# power.net
KiCad netlist of a schematic drawn in EAGLE
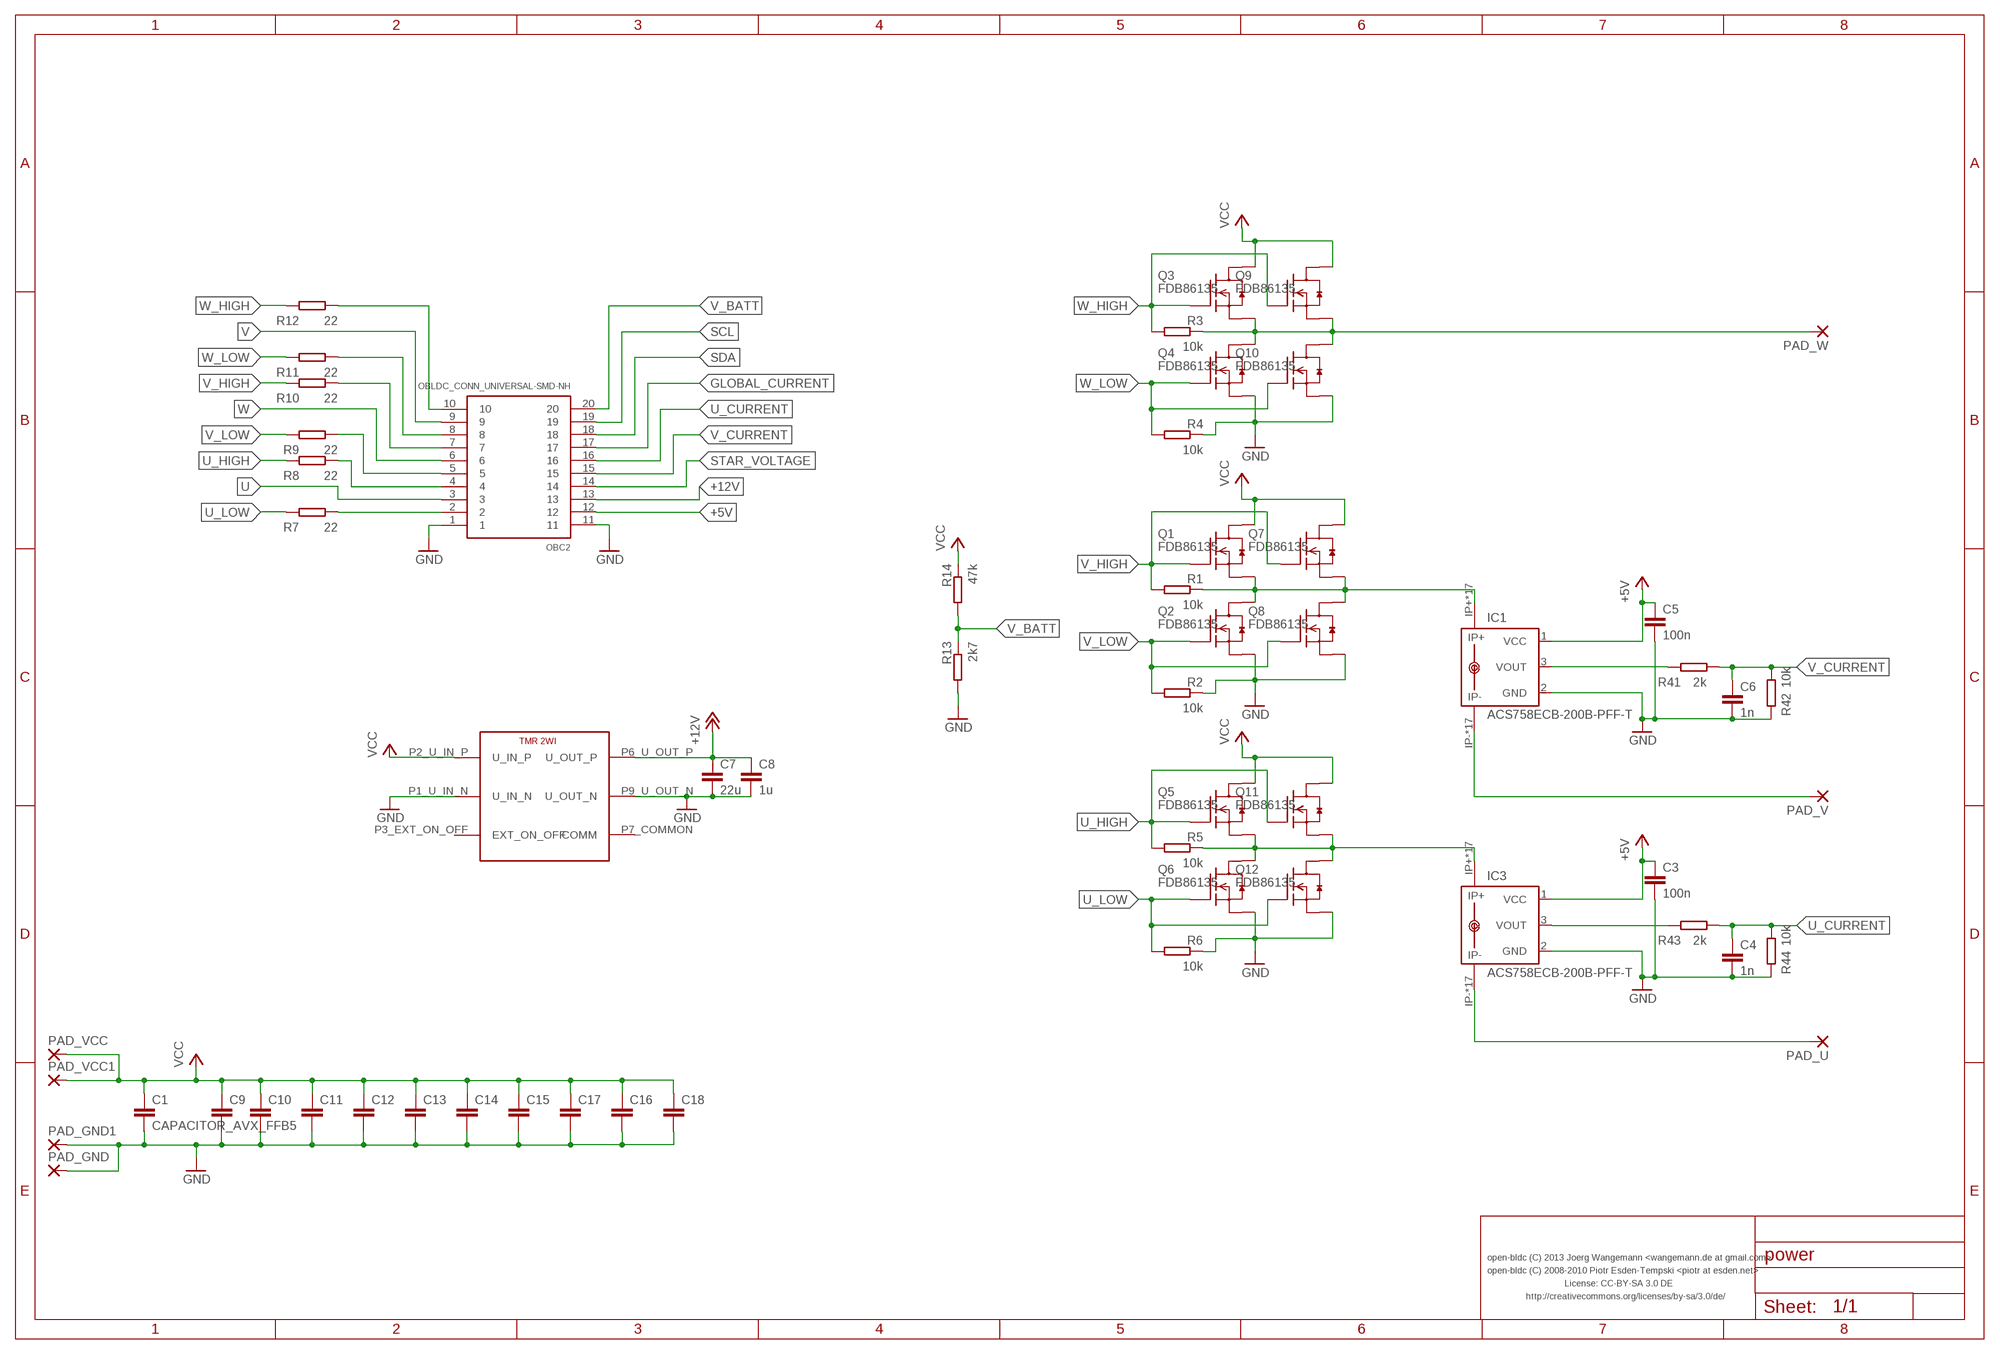
[diagram p0: schematic, sheet 1]

(export (version "E")
  (design (tool "Eeschema 10.0.6"))
  (components
    (comp (ref "C1")
      (value "CAPACITOR_AVX_FFB5")
      (footprint "eagle-import:AVX_FFB5")
      (libsource (lib "eagle-import") (part "CAPACITOR_AVX_FFB5"))
    )
    (comp (ref "C3")
      (value "100n")
      (footprint "eagle-import:0603-CAP")
      (libsource (lib "eagle-import") (part "CAPACITOR-0603"))
    )
    (comp (ref "C4")
      (value "1n")
      (footprint "eagle-import:0603-CAP")
      (libsource (lib "eagle-import") (part "CAPACITOR-0603"))
    )
    (comp (ref "C5")
      (value "100n")
      (footprint "eagle-import:0603-CAP")
      (libsource (lib "eagle-import") (part "CAPACITOR-0603"))
    )
    (comp (ref "C6")
      (value "1n")
      (footprint "eagle-import:0603-CAP")
      (libsource (lib "eagle-import") (part "CAPACITOR-0603"))
    )
    (comp (ref "C7")
      (value "22u")
      (footprint "eagle-import:C2220K")
      (libsource (lib "eagle-import") (part "C-EUC2220K"))
    )
    (comp (ref "C8")
      (value "1u")
      (footprint "eagle-import:C1206")
      (libsource (lib "eagle-import") (part "C-EUC1206"))
    )
    (comp (ref "C9")
      (value "C-EUC2220K")
      (footprint "eagle-import:C2220K")
      (libsource (lib "eagle-import") (part "C-EUC2220K"))
    )
    (comp (ref "C10")
      (value "C-EUC2220K")
      (footprint "eagle-import:C2220K")
      (libsource (lib "eagle-import") (part "C-EUC2220K"))
    )
    (comp (ref "C11")
      (value "C-EUC2220K")
      (footprint "eagle-import:C2220K")
      (libsource (lib "eagle-import") (part "C-EUC2220K"))
    )
    (comp (ref "C12")
      (value "C-EUC2220K")
      (footprint "eagle-import:C2220K")
      (libsource (lib "eagle-import") (part "C-EUC2220K"))
    )
    (comp (ref "C13")
      (value "C-EUC2220K")
      (footprint "eagle-import:C2220K")
      (libsource (lib "eagle-import") (part "C-EUC2220K"))
    )
    (comp (ref "C14")
      (value "C-EUC2220K")
      (footprint "eagle-import:C2220K")
      (libsource (lib "eagle-import") (part "C-EUC2220K"))
    )
    (comp (ref "C15")
      (value "C-EUC2220K")
      (footprint "eagle-import:C2220K")
      (libsource (lib "eagle-import") (part "C-EUC2220K"))
    )
    (comp (ref "C16")
      (value "C-EUC2220K")
      (footprint "eagle-import:C2220K")
      (libsource (lib "eagle-import") (part "C-EUC2220K"))
    )
    (comp (ref "C17")
      (value "C-EUC2220K")
      (footprint "eagle-import:C2220K")
      (libsource (lib "eagle-import") (part "C-EUC2220K"))
    )
    (comp (ref "C18")
      (value "C-EUC2220K")
      (footprint "eagle-import:C2220K")
      (libsource (lib "eagle-import") (part "C-EUC2220K"))
    )
    (comp (ref "IC1")
      (value "ACS758ECB-200B-PFF-T")
      (footprint "eagle-import:CB-PFF")
      (libsource (lib "eagle-import") (part "ACS758ECB-200B-PFF-T"))
    )
    (comp (ref "IC3")
      (value "ACS758ECB-200B-PFF-T")
      (footprint "eagle-import:CB-PFF")
      (libsource (lib "eagle-import") (part "ACS758ECB-200B-PFF-T"))
    )
    (comp (ref "OBC2")
      (value "OBLDC_CONN_UNIVERSAL-SMD-NH")
      (footprint "eagle-import:OBLDC_CONN_SMD_NO_HOLES")
      (libsource (lib "eagle-import") (part "OBLDC_CONN_UNIVERSAL-SMD-NH"))
    )
    (comp (ref "PAD_GND")
      (value "WIREPAD-2MM")
      (footprint "eagle-import:WIREPAD_2MM")
      (libsource (lib "eagle-import") (part "WIREPAD-2MM"))
    )
    (comp (ref "PAD_GND1")
      (value "WIREPAD-2MM")
      (footprint "eagle-import:WIREPAD_2MM")
      (libsource (lib "eagle-import") (part "WIREPAD-2MM"))
    )
    (comp (ref "PAD_U")
      (value "WIREPAD-2MM")
      (footprint "eagle-import:WIREPAD_2MM")
      (libsource (lib "eagle-import") (part "WIREPAD-2MM"))
    )
    (comp (ref "PAD_V")
      (value "WIREPAD-2MM")
      (footprint "eagle-import:WIREPAD_2MM")
      (libsource (lib "eagle-import") (part "WIREPAD-2MM"))
    )
    (comp (ref "PAD_VCC")
      (value "WIREPAD-2MM")
      (footprint "eagle-import:WIREPAD_2MM")
      (libsource (lib "eagle-import") (part "WIREPAD-2MM"))
    )
    (comp (ref "PAD_VCC1")
      (value "WIREPAD-2MM")
      (footprint "eagle-import:WIREPAD_2MM")
      (libsource (lib "eagle-import") (part "WIREPAD-2MM"))
    )
    (comp (ref "PAD_W")
      (value "WIREPAD-2MM")
      (footprint "eagle-import:WIREPAD_2MM")
      (libsource (lib "eagle-import") (part "WIREPAD-2MM"))
    )
    (comp (ref "Q1")
      (value "FDB86135")
      (footprint "eagle-import:DPAK")
      (libsource (lib "eagle-import") (part "FDB86135"))
    )
    (comp (ref "Q2")
      (value "FDB86135")
      (footprint "eagle-import:DPAK")
      (libsource (lib "eagle-import") (part "FDB86135"))
    )
    (comp (ref "Q3")
      (value "FDB86135")
      (footprint "eagle-import:DPAK")
      (libsource (lib "eagle-import") (part "FDB86135"))
    )
    (comp (ref "Q4")
      (value "FDB86135")
      (footprint "eagle-import:DPAK")
      (libsource (lib "eagle-import") (part "FDB86135"))
    )
    (comp (ref "Q5")
      (value "FDB86135")
      (footprint "eagle-import:DPAK")
      (libsource (lib "eagle-import") (part "FDB86135"))
    )
    (comp (ref "Q6")
      (value "FDB86135")
      (footprint "eagle-import:DPAK")
      (libsource (lib "eagle-import") (part "FDB86135"))
    )
    (comp (ref "Q7")
      (value "FDB86135")
      (footprint "eagle-import:DPAK")
      (libsource (lib "eagle-import") (part "FDB86135"))
    )
    (comp (ref "Q8")
      (value "FDB86135")
      (footprint "eagle-import:DPAK")
      (libsource (lib "eagle-import") (part "FDB86135"))
    )
    (comp (ref "Q9")
      (value "FDB86135")
      (footprint "eagle-import:DPAK")
      (libsource (lib "eagle-import") (part "FDB86135"))
    )
    (comp (ref "Q10")
      (value "FDB86135")
      (footprint "eagle-import:DPAK")
      (libsource (lib "eagle-import") (part "FDB86135"))
    )
    (comp (ref "Q11")
      (value "FDB86135")
      (footprint "eagle-import:DPAK")
      (libsource (lib "eagle-import") (part "FDB86135"))
    )
    (comp (ref "Q12")
      (value "FDB86135")
      (footprint "eagle-import:DPAK")
      (libsource (lib "eagle-import") (part "FDB86135"))
    )
    (comp (ref "R1")
      (value "10k")
      (footprint "eagle-import:0603-SF-RES")
      (libsource (lib "eagle-import") (part "RESISTOR-0603SF"))
    )
    (comp (ref "R2")
      (value "10k")
      (footprint "eagle-import:0603-SF-RES")
      (libsource (lib "eagle-import") (part "RESISTOR-0603SF"))
    )
    (comp (ref "R3")
      (value "10k")
      (footprint "eagle-import:0603-SF-RES")
      (libsource (lib "eagle-import") (part "RESISTOR-0603SF"))
    )
    (comp (ref "R4")
      (value "10k")
      (footprint "eagle-import:0603-SF-RES")
      (libsource (lib "eagle-import") (part "RESISTOR-0603SF"))
    )
    (comp (ref "R5")
      (value "10k")
      (footprint "eagle-import:0603-SF-RES")
      (libsource (lib "eagle-import") (part "RESISTOR-0603SF"))
    )
    (comp (ref "R6")
      (value "10k")
      (footprint "eagle-import:0603-SF-RES")
      (libsource (lib "eagle-import") (part "RESISTOR-0603SF"))
    )
    (comp (ref "R7")
      (value "22")
      (footprint "eagle-import:1206-RES")
      (libsource (lib "eagle-import") (part "RESISTOR-1206"))
    )
    (comp (ref "R8")
      (value "22")
      (footprint "eagle-import:1206-RES")
      (libsource (lib "eagle-import") (part "RESISTOR-1206"))
    )
    (comp (ref "R9")
      (value "22")
      (footprint "eagle-import:1206-RES")
      (libsource (lib "eagle-import") (part "RESISTOR-1206"))
    )
    (comp (ref "R10")
      (value "22")
      (footprint "eagle-import:1206-RES")
      (libsource (lib "eagle-import") (part "RESISTOR-1206"))
    )
    (comp (ref "R11")
      (value "22")
      (footprint "eagle-import:1206-RES")
      (libsource (lib "eagle-import") (part "RESISTOR-1206"))
    )
    (comp (ref "R12")
      (value "22")
      (footprint "eagle-import:1206-RES")
      (libsource (lib "eagle-import") (part "RESISTOR-1206"))
    )
    (comp (ref "R13")
      (value "2k7")
      (footprint "eagle-import:1206-RES")
      (libsource (lib "eagle-import") (part "RESISTOR-1206"))
    )
    (comp (ref "R14")
      (value "47k")
      (footprint "eagle-import:1206-RES")
      (libsource (lib "eagle-import") (part "RESISTOR-1206"))
    )
    (comp (ref "R41")
      (value "2k")
      (footprint "eagle-import:0603-RES")
      (libsource (lib "eagle-import") (part "RESISTOR-0603"))
    )
    (comp (ref "R42")
      (value "10k")
      (footprint "eagle-import:0603-RES")
      (libsource (lib "eagle-import") (part "RESISTOR-0603"))
    )
    (comp (ref "R43")
      (value "2k")
      (footprint "eagle-import:0603-RES")
      (libsource (lib "eagle-import") (part "RESISTOR-0603"))
    )
    (comp (ref "R44")
      (value "10k")
      (footprint "eagle-import:0603-RES")
      (libsource (lib "eagle-import") (part "RESISTOR-0603"))
    )
    (comp (ref "U$2")
      (value "TRACO_TMR_2WI")
      (footprint "eagle-import:TRACO_TMR_2WI")
      (libsource (lib "eagle-import") (part "TRACO_TMR_2WI"))
    )
  )
  (nets
    (net (code "1") (name "+5V") (class "Default")
      (node (ref "C3") (pin "P$1") (pinfunction "1_P$1") (pintype "passive"))
      (node (ref "C5") (pin "P$1") (pinfunction "1_P$1") (pintype "passive"))
      (node (ref "IC1") (pin "1") (pinfunction "VCC_1") (pintype "power_in"))
      (node (ref "IC3") (pin "1") (pinfunction "VCC_1") (pintype "power_in"))
      (node (ref "OBC2") (pin "12") (pinfunction "12_12") (pintype "bidirectional"))
    )
    (net (code "2") (name "+12V") (class "Default")
      (node (ref "C7") (pin "1") (pinfunction "1_1") (pintype "passive"))
      (node (ref "C8") (pin "1") (pinfunction "1_1") (pintype "passive"))
      (node (ref "OBC2") (pin "13") (pinfunction "13_13") (pintype "bidirectional"))
      (node (ref "U$2") (pin "P6_U_OUT_P") (pinfunction "U_OUT_P_P6_U_OUT_P") (pintype "bidirectional"))
    )
    (net (code "3") (name "GLOBAL_CURRENT") (class "Default")
      (node (ref "OBC2") (pin "17") (pinfunction "17_17") (pintype "bidirectional"))
    )
    (net (code "4") (name "GND") (class "Default")
      (node (ref "C1") (pin "P$2") (pinfunction "2_P$2") (pintype "passive"))
      (node (ref "C10") (pin "2") (pinfunction "2_2") (pintype "passive"))
      (node (ref "C11") (pin "2") (pinfunction "2_2") (pintype "passive"))
      (node (ref "C12") (pin "2") (pinfunction "2_2") (pintype "passive"))
      (node (ref "C13") (pin "2") (pinfunction "2_2") (pintype "passive"))
      (node (ref "C14") (pin "2") (pinfunction "2_2") (pintype "passive"))
      (node (ref "C15") (pin "2") (pinfunction "2_2") (pintype "passive"))
      (node (ref "C16") (pin "2") (pinfunction "2_2") (pintype "passive"))
      (node (ref "C17") (pin "2") (pinfunction "2_2") (pintype "passive"))
      (node (ref "C18") (pin "2") (pinfunction "2_2") (pintype "passive"))
      (node (ref "C3") (pin "P$2") (pinfunction "2_P$2") (pintype "passive"))
      (node (ref "C4") (pin "P$2") (pinfunction "2_P$2") (pintype "passive"))
      (node (ref "C5") (pin "P$2") (pinfunction "2_P$2") (pintype "passive"))
      (node (ref "C6") (pin "P$2") (pinfunction "2_P$2") (pintype "passive"))
      (node (ref "C7") (pin "2") (pinfunction "2_2") (pintype "passive"))
      (node (ref "C8") (pin "2") (pinfunction "2_2") (pintype "passive"))
      (node (ref "C9") (pin "2") (pinfunction "2_2") (pintype "passive"))
      (node (ref "IC1") (pin "2") (pinfunction "GND_2") (pintype "power_in"))
      (node (ref "IC3") (pin "2") (pinfunction "GND_2") (pintype "power_in"))
      (node (ref "OBC2") (pin "1") (pinfunction "1_1") (pintype "bidirectional"))
      (node (ref "OBC2") (pin "11") (pinfunction "11_11") (pintype "bidirectional"))
      (node (ref "PAD_GND") (pin "1") (pinfunction "P_1") (pintype "passive"))
      (node (ref "PAD_GND1") (pin "1") (pinfunction "P_1") (pintype "passive"))
      (node (ref "Q10") (pin "3") (pinfunction "S_3") (pintype "passive"))
      (node (ref "Q12") (pin "3") (pinfunction "S_3") (pintype "passive"))
      (node (ref "Q2") (pin "3") (pinfunction "S_3") (pintype "passive"))
      (node (ref "Q4") (pin "3") (pinfunction "S_3") (pintype "passive"))
      (node (ref "Q6") (pin "3") (pinfunction "S_3") (pintype "passive"))
      (node (ref "Q8") (pin "3") (pinfunction "S_3") (pintype "passive"))
      (node (ref "R13") (pin "P$2") (pinfunction "2_P$2") (pintype "passive"))
      (node (ref "R2") (pin "1") (pinfunction "1_1") (pintype "passive"))
      (node (ref "R4") (pin "1") (pinfunction "1_1") (pintype "passive"))
      (node (ref "R42") (pin "P$2") (pinfunction "2_P$2") (pintype "passive"))
      (node (ref "R44") (pin "P$2") (pinfunction "2_P$2") (pintype "passive"))
      (node (ref "R6") (pin "1") (pinfunction "1_1") (pintype "passive"))
      (node (ref "U$2") (pin "P1_U_IN_N") (pinfunction "U_IN_N_P1_U_IN_N") (pintype "bidirectional"))
      (node (ref "U$2") (pin "P9_U_OUT_N") (pinfunction "U_OUT_N_P9_U_OUT_N") (pintype "bidirectional"))
    )
    (net (code "5") (name "Net-(IC1-VOUT)") (class "Default")
      (node (ref "IC1") (pin "3") (pinfunction "VOUT_3") (pintype "output"))
      (node (ref "R41") (pin "P$2") (pinfunction "2_P$2") (pintype "passive"))
    )
    (net (code "6") (name "Net-(IC3-VOUT)") (class "Default")
      (node (ref "IC3") (pin "3") (pinfunction "VOUT_3") (pintype "output"))
      (node (ref "R43") (pin "P$2") (pinfunction "2_P$2") (pintype "passive"))
    )
    (net (code "7") (name "Net-(PAD_U-P)") (class "Default")
      (node (ref "IC3") (pin "IP-") (pinfunction "IP-_IP-") (pintype "passive"))
      (node (ref "IC3") (pin "IP-@10") (pinfunction "IP-_IP-@10") (pintype "passive"))
      (node (ref "IC3") (pin "IP-@11") (pinfunction "IP-_IP-@11") (pintype "passive"))
      (node (ref "IC3") (pin "IP-@12") (pinfunction "IP-_IP-@12") (pintype "passive"))
      (node (ref "IC3") (pin "IP-@13") (pinfunction "IP-_IP-@13") (pintype "passive"))
      (node (ref "IC3") (pin "IP-@14") (pinfunction "IP-_IP-@14") (pintype "passive"))
      (node (ref "IC3") (pin "IP-@15") (pinfunction "IP-_IP-@15") (pintype "passive"))
      (node (ref "IC3") (pin "IP-@16") (pinfunction "IP-_IP-@16") (pintype "passive"))
      (node (ref "IC3") (pin "IP-@17") (pinfunction "IP-_IP-@17") (pintype "passive"))
      (node (ref "IC3") (pin "IP-@2") (pinfunction "IP-_IP-@2") (pintype "passive"))
      (node (ref "IC3") (pin "IP-@3") (pinfunction "IP-_IP-@3") (pintype "passive"))
      (node (ref "IC3") (pin "IP-@4") (pinfunction "IP-_IP-@4") (pintype "passive"))
      (node (ref "IC3") (pin "IP-@5") (pinfunction "IP-_IP-@5") (pintype "passive"))
      (node (ref "IC3") (pin "IP-@6") (pinfunction "IP-_IP-@6") (pintype "passive"))
      (node (ref "IC3") (pin "IP-@7") (pinfunction "IP-_IP-@7") (pintype "passive"))
      (node (ref "IC3") (pin "IP-@8") (pinfunction "IP-_IP-@8") (pintype "passive"))
      (node (ref "IC3") (pin "IP-@9") (pinfunction "IP-_IP-@9") (pintype "passive"))
      (node (ref "PAD_U") (pin "1") (pinfunction "P_1") (pintype "passive"))
    )
    (net (code "8") (name "Net-(PAD_V-P)") (class "Default")
      (node (ref "IC1") (pin "IP-") (pinfunction "IP-_IP-") (pintype "passive"))
      (node (ref "IC1") (pin "IP-@10") (pinfunction "IP-_IP-@10") (pintype "passive"))
      (node (ref "IC1") (pin "IP-@11") (pinfunction "IP-_IP-@11") (pintype "passive"))
      (node (ref "IC1") (pin "IP-@12") (pinfunction "IP-_IP-@12") (pintype "passive"))
      (node (ref "IC1") (pin "IP-@13") (pinfunction "IP-_IP-@13") (pintype "passive"))
      (node (ref "IC1") (pin "IP-@14") (pinfunction "IP-_IP-@14") (pintype "passive"))
      (node (ref "IC1") (pin "IP-@15") (pinfunction "IP-_IP-@15") (pintype "passive"))
      (node (ref "IC1") (pin "IP-@16") (pinfunction "IP-_IP-@16") (pintype "passive"))
      (node (ref "IC1") (pin "IP-@17") (pinfunction "IP-_IP-@17") (pintype "passive"))
      (node (ref "IC1") (pin "IP-@2") (pinfunction "IP-_IP-@2") (pintype "passive"))
      (node (ref "IC1") (pin "IP-@3") (pinfunction "IP-_IP-@3") (pintype "passive"))
      (node (ref "IC1") (pin "IP-@4") (pinfunction "IP-_IP-@4") (pintype "passive"))
      (node (ref "IC1") (pin "IP-@5") (pinfunction "IP-_IP-@5") (pintype "passive"))
      (node (ref "IC1") (pin "IP-@6") (pinfunction "IP-_IP-@6") (pintype "passive"))
      (node (ref "IC1") (pin "IP-@7") (pinfunction "IP-_IP-@7") (pintype "passive"))
      (node (ref "IC1") (pin "IP-@8") (pinfunction "IP-_IP-@8") (pintype "passive"))
      (node (ref "IC1") (pin "IP-@9") (pinfunction "IP-_IP-@9") (pintype "passive"))
      (node (ref "PAD_V") (pin "1") (pinfunction "P_1") (pintype "passive"))
    )
    (net (code "9") (name "Net-(R7-1)") (class "Default")
      (node (ref "OBC2") (pin "2") (pinfunction "2_2") (pintype "bidirectional"))
      (node (ref "R7") (pin "P$1") (pinfunction "1_P$1") (pintype "passive"))
    )
    (net (code "10") (name "Net-(R8-1)") (class "Default")
      (node (ref "OBC2") (pin "4") (pinfunction "4_4") (pintype "bidirectional"))
      (node (ref "R8") (pin "P$1") (pinfunction "1_P$1") (pintype "passive"))
    )
    (net (code "11") (name "Net-(R9-1)") (class "Default")
      (node (ref "OBC2") (pin "5") (pinfunction "5_5") (pintype "bidirectional"))
      (node (ref "R9") (pin "P$1") (pinfunction "1_P$1") (pintype "passive"))
    )
    (net (code "12") (name "Net-(R10-1)") (class "Default")
      (node (ref "OBC2") (pin "7") (pinfunction "7_7") (pintype "bidirectional"))
      (node (ref "R10") (pin "P$1") (pinfunction "1_P$1") (pintype "passive"))
    )
    (net (code "13") (name "Net-(R11-1)") (class "Default")
      (node (ref "OBC2") (pin "8") (pinfunction "8_8") (pintype "bidirectional"))
      (node (ref "R11") (pin "P$1") (pinfunction "1_P$1") (pintype "passive"))
    )
    (net (code "14") (name "Net-(R12-1)") (class "Default")
      (node (ref "OBC2") (pin "10") (pinfunction "10_10") (pintype "bidirectional"))
      (node (ref "R12") (pin "P$1") (pinfunction "1_P$1") (pintype "passive"))
    )
    (net (code "15") (name "SCL") (class "Default")
      (node (ref "OBC2") (pin "19") (pinfunction "19_19") (pintype "bidirectional"))
    )
    (net (code "16") (name "SDA") (class "Default")
      (node (ref "OBC2") (pin "18") (pinfunction "18_18") (pintype "bidirectional"))
    )
    (net (code "17") (name "STAR_VOLTAGE") (class "Default")
      (node (ref "OBC2") (pin "14") (pinfunction "14_14") (pintype "bidirectional"))
    )
    (net (code "18") (name "U") (class "Default")
      (node (ref "IC3") (pin "IP+") (pinfunction "IP+_IP+") (pintype "passive"))
      (node (ref "IC3") (pin "IP+@10") (pinfunction "IP+_IP+@10") (pintype "passive"))
      (node (ref "IC3") (pin "IP+@11") (pinfunction "IP+_IP+@11") (pintype "passive"))
      (node (ref "IC3") (pin "IP+@12") (pinfunction "IP+_IP+@12") (pintype "passive"))
      (node (ref "IC3") (pin "IP+@13") (pinfunction "IP+_IP+@13") (pintype "passive"))
      (node (ref "IC3") (pin "IP+@14") (pinfunction "IP+_IP+@14") (pintype "passive"))
      (node (ref "IC3") (pin "IP+@15") (pinfunction "IP+_IP+@15") (pintype "passive"))
      (node (ref "IC3") (pin "IP+@16") (pinfunction "IP+_IP+@16") (pintype "passive"))
      (node (ref "IC3") (pin "IP+@17") (pinfunction "IP+_IP+@17") (pintype "passive"))
      (node (ref "IC3") (pin "IP+@2") (pinfunction "IP+_IP+@2") (pintype "passive"))
      (node (ref "IC3") (pin "IP+@3") (pinfunction "IP+_IP+@3") (pintype "passive"))
      (node (ref "IC3") (pin "IP+@4") (pinfunction "IP+_IP+@4") (pintype "passive"))
      (node (ref "IC3") (pin "IP+@5") (pinfunction "IP+_IP+@5") (pintype "passive"))
      (node (ref "IC3") (pin "IP+@6") (pinfunction "IP+_IP+@6") (pintype "passive"))
      (node (ref "IC3") (pin "IP+@7") (pinfunction "IP+_IP+@7") (pintype "passive"))
      (node (ref "IC3") (pin "IP+@8") (pinfunction "IP+_IP+@8") (pintype "passive"))
      (node (ref "IC3") (pin "IP+@9") (pinfunction "IP+_IP+@9") (pintype "passive"))
      (node (ref "OBC2") (pin "3") (pinfunction "3_3") (pintype "bidirectional"))
      (node (ref "Q11") (pin "3") (pinfunction "S_3") (pintype "passive"))
      (node (ref "Q12") (pin "P$1") (pinfunction "D_P$1") (pintype "passive"))
      (node (ref "Q5") (pin "3") (pinfunction "S_3") (pintype "passive"))
      (node (ref "Q6") (pin "P$1") (pinfunction "D_P$1") (pintype "passive"))
      (node (ref "R5") (pin "1") (pinfunction "1_1") (pintype "passive"))
    )
    (net (code "19") (name "U_CURRENT") (class "Default")
      (node (ref "C4") (pin "P$1") (pinfunction "1_P$1") (pintype "passive"))
      (node (ref "OBC2") (pin "16") (pinfunction "16_16") (pintype "bidirectional"))
      (node (ref "R43") (pin "P$1") (pinfunction "1_P$1") (pintype "passive"))
      (node (ref "R44") (pin "P$1") (pinfunction "1_P$1") (pintype "passive"))
    )
    (net (code "20") (name "U_HIGH") (class "Default")
      (node (ref "Q11") (pin "1") (pinfunction "G_1") (pintype "passive"))
      (node (ref "Q5") (pin "1") (pinfunction "G_1") (pintype "passive"))
      (node (ref "R5") (pin "2") (pinfunction "2_2") (pintype "passive"))
      (node (ref "R8") (pin "P$2") (pinfunction "2_P$2") (pintype "passive"))
    )
    (net (code "21") (name "U_LOW") (class "Default")
      (node (ref "Q12") (pin "1") (pinfunction "G_1") (pintype "passive"))
      (node (ref "Q6") (pin "1") (pinfunction "G_1") (pintype "passive"))
      (node (ref "R6") (pin "2") (pinfunction "2_2") (pintype "passive"))
      (node (ref "R7") (pin "P$2") (pinfunction "2_P$2") (pintype "passive"))
    )
    (net (code "22") (name "V") (class "Default")
      (node (ref "IC1") (pin "IP+") (pinfunction "IP+_IP+") (pintype "passive"))
      (node (ref "IC1") (pin "IP+@10") (pinfunction "IP+_IP+@10") (pintype "passive"))
      (node (ref "IC1") (pin "IP+@11") (pinfunction "IP+_IP+@11") (pintype "passive"))
      (node (ref "IC1") (pin "IP+@12") (pinfunction "IP+_IP+@12") (pintype "passive"))
      (node (ref "IC1") (pin "IP+@13") (pinfunction "IP+_IP+@13") (pintype "passive"))
      (node (ref "IC1") (pin "IP+@14") (pinfunction "IP+_IP+@14") (pintype "passive"))
      (node (ref "IC1") (pin "IP+@15") (pinfunction "IP+_IP+@15") (pintype "passive"))
      (node (ref "IC1") (pin "IP+@16") (pinfunction "IP+_IP+@16") (pintype "passive"))
      (node (ref "IC1") (pin "IP+@17") (pinfunction "IP+_IP+@17") (pintype "passive"))
      (node (ref "IC1") (pin "IP+@2") (pinfunction "IP+_IP+@2") (pintype "passive"))
      (node (ref "IC1") (pin "IP+@3") (pinfunction "IP+_IP+@3") (pintype "passive"))
      (node (ref "IC1") (pin "IP+@4") (pinfunction "IP+_IP+@4") (pintype "passive"))
      (node (ref "IC1") (pin "IP+@5") (pinfunction "IP+_IP+@5") (pintype "passive"))
      (node (ref "IC1") (pin "IP+@6") (pinfunction "IP+_IP+@6") (pintype "passive"))
      (node (ref "IC1") (pin "IP+@7") (pinfunction "IP+_IP+@7") (pintype "passive"))
      (node (ref "IC1") (pin "IP+@8") (pinfunction "IP+_IP+@8") (pintype "passive"))
      (node (ref "IC1") (pin "IP+@9") (pinfunction "IP+_IP+@9") (pintype "passive"))
      (node (ref "OBC2") (pin "9") (pinfunction "9_9") (pintype "bidirectional"))
      (node (ref "Q1") (pin "3") (pinfunction "S_3") (pintype "passive"))
      (node (ref "Q2") (pin "P$1") (pinfunction "D_P$1") (pintype "passive"))
      (node (ref "Q7") (pin "3") (pinfunction "S_3") (pintype "passive"))
      (node (ref "Q8") (pin "P$1") (pinfunction "D_P$1") (pintype "passive"))
      (node (ref "R1") (pin "1") (pinfunction "1_1") (pintype "passive"))
    )
    (net (code "23") (name "VCC") (class "Default")
      (node (ref "C1") (pin "P$1") (pinfunction "1_P$1") (pintype "passive"))
      (node (ref "C10") (pin "1") (pinfunction "1_1") (pintype "passive"))
      (node (ref "C11") (pin "1") (pinfunction "1_1") (pintype "passive"))
      (node (ref "C12") (pin "1") (pinfunction "1_1") (pintype "passive"))
      (node (ref "C13") (pin "1") (pinfunction "1_1") (pintype "passive"))
      (node (ref "C14") (pin "1") (pinfunction "1_1") (pintype "passive"))
      (node (ref "C15") (pin "1") (pinfunction "1_1") (pintype "passive"))
      (node (ref "C16") (pin "1") (pinfunction "1_1") (pintype "passive"))
      (node (ref "C17") (pin "1") (pinfunction "1_1") (pintype "passive"))
      (node (ref "C18") (pin "1") (pinfunction "1_1") (pintype "passive"))
      (node (ref "C9") (pin "1") (pinfunction "1_1") (pintype "passive"))
      (node (ref "PAD_VCC") (pin "1") (pinfunction "P_1") (pintype "passive"))
      (node (ref "PAD_VCC1") (pin "1") (pinfunction "P_1") (pintype "passive"))
      (node (ref "Q1") (pin "P$1") (pinfunction "D_P$1") (pintype "passive"))
      (node (ref "Q11") (pin "P$1") (pinfunction "D_P$1") (pintype "passive"))
      (node (ref "Q3") (pin "P$1") (pinfunction "D_P$1") (pintype "passive"))
      (node (ref "Q5") (pin "P$1") (pinfunction "D_P$1") (pintype "passive"))
      (node (ref "Q7") (pin "P$1") (pinfunction "D_P$1") (pintype "passive"))
      (node (ref "Q9") (pin "P$1") (pinfunction "D_P$1") (pintype "passive"))
      (node (ref "R14") (pin "P$1") (pinfunction "1_P$1") (pintype "passive"))
      (node (ref "U$2") (pin "P2_U_IN_P") (pinfunction "U_IN_P_P2_U_IN_P") (pintype "bidirectional"))
    )
    (net (code "24") (name "V_BATT") (class "Default")
      (node (ref "OBC2") (pin "20") (pinfunction "20_20") (pintype "bidirectional"))
      (node (ref "R13") (pin "P$1") (pinfunction "1_P$1") (pintype "passive"))
      (node (ref "R14") (pin "P$2") (pinfunction "2_P$2") (pintype "passive"))
    )
    (net (code "25") (name "V_CURRENT") (class "Default")
      (node (ref "C6") (pin "P$1") (pinfunction "1_P$1") (pintype "passive"))
      (node (ref "OBC2") (pin "15") (pinfunction "15_15") (pintype "bidirectional"))
      (node (ref "R41") (pin "P$1") (pinfunction "1_P$1") (pintype "passive"))
      (node (ref "R42") (pin "P$1") (pinfunction "1_P$1") (pintype "passive"))
    )
    (net (code "26") (name "V_HIGH") (class "Default")
      (node (ref "Q3") (pin "1") (pinfunction "G_1") (pintype "passive"))
      (node (ref "Q9") (pin "1") (pinfunction "G_1") (pintype "passive"))
      (node (ref "R10") (pin "P$2") (pinfunction "2_P$2") (pintype "passive"))
      (node (ref "R3") (pin "2") (pinfunction "2_2") (pintype "passive"))
    )
    (net (code "27") (name "V_LOW") (class "Default")
      (node (ref "Q10") (pin "1") (pinfunction "G_1") (pintype "passive"))
      (node (ref "Q4") (pin "1") (pinfunction "G_1") (pintype "passive"))
      (node (ref "R4") (pin "2") (pinfunction "2_2") (pintype "passive"))
      (node (ref "R9") (pin "P$2") (pinfunction "2_P$2") (pintype "passive"))
    )
    (net (code "28") (name "W") (class "Default")
      (node (ref "OBC2") (pin "6") (pinfunction "6_6") (pintype "bidirectional"))
      (node (ref "PAD_W") (pin "1") (pinfunction "P_1") (pintype "passive"))
      (node (ref "Q10") (pin "P$1") (pinfunction "D_P$1") (pintype "passive"))
      (node (ref "Q3") (pin "3") (pinfunction "S_3") (pintype "passive"))
      (node (ref "Q4") (pin "P$1") (pinfunction "D_P$1") (pintype "passive"))
      (node (ref "Q9") (pin "3") (pinfunction "S_3") (pintype "passive"))
      (node (ref "R3") (pin "1") (pinfunction "1_1") (pintype "passive"))
    )
    (net (code "29") (name "W_HIGH") (class "Default")
      (node (ref "Q1") (pin "1") (pinfunction "G_1") (pintype "passive"))
      (node (ref "Q7") (pin "1") (pinfunction "G_1") (pintype "passive"))
      (node (ref "R1") (pin "2") (pinfunction "2_2") (pintype "passive"))
      (node (ref "R12") (pin "P$2") (pinfunction "2_P$2") (pintype "passive"))
    )
    (net (code "30") (name "W_LOW") (class "Default")
      (node (ref "Q2") (pin "1") (pinfunction "G_1") (pintype "passive"))
      (node (ref "Q8") (pin "1") (pinfunction "G_1") (pintype "passive"))
      (node (ref "R11") (pin "P$2") (pinfunction "2_P$2") (pintype "passive"))
      (node (ref "R2") (pin "2") (pinfunction "2_2") (pintype "passive"))
    )
    (net (code "31") (name "unconnected-(U$2-COMM-PadP7_COMMON)") (class "Default")
      (node (ref "U$2") (pin "P7_COMMON") (pinfunction "COMM_P7_COMMON") (pintype "bidirectional"))
    )
    (net (code "32") (name "unconnected-(U$2-EXT_ON_OFF-PadP3_EXT_ON_OFF)") (class "Default")
      (node (ref "U$2") (pin "P3_EXT_ON_OFF") (pinfunction "EXT_ON_OFF_P3_EXT_ON_OFF") (pintype "bidirectional"))
    )
  )
)
